# hot_er_lutownica.net
KiCad netlist of a schematic drawn in EAGLE
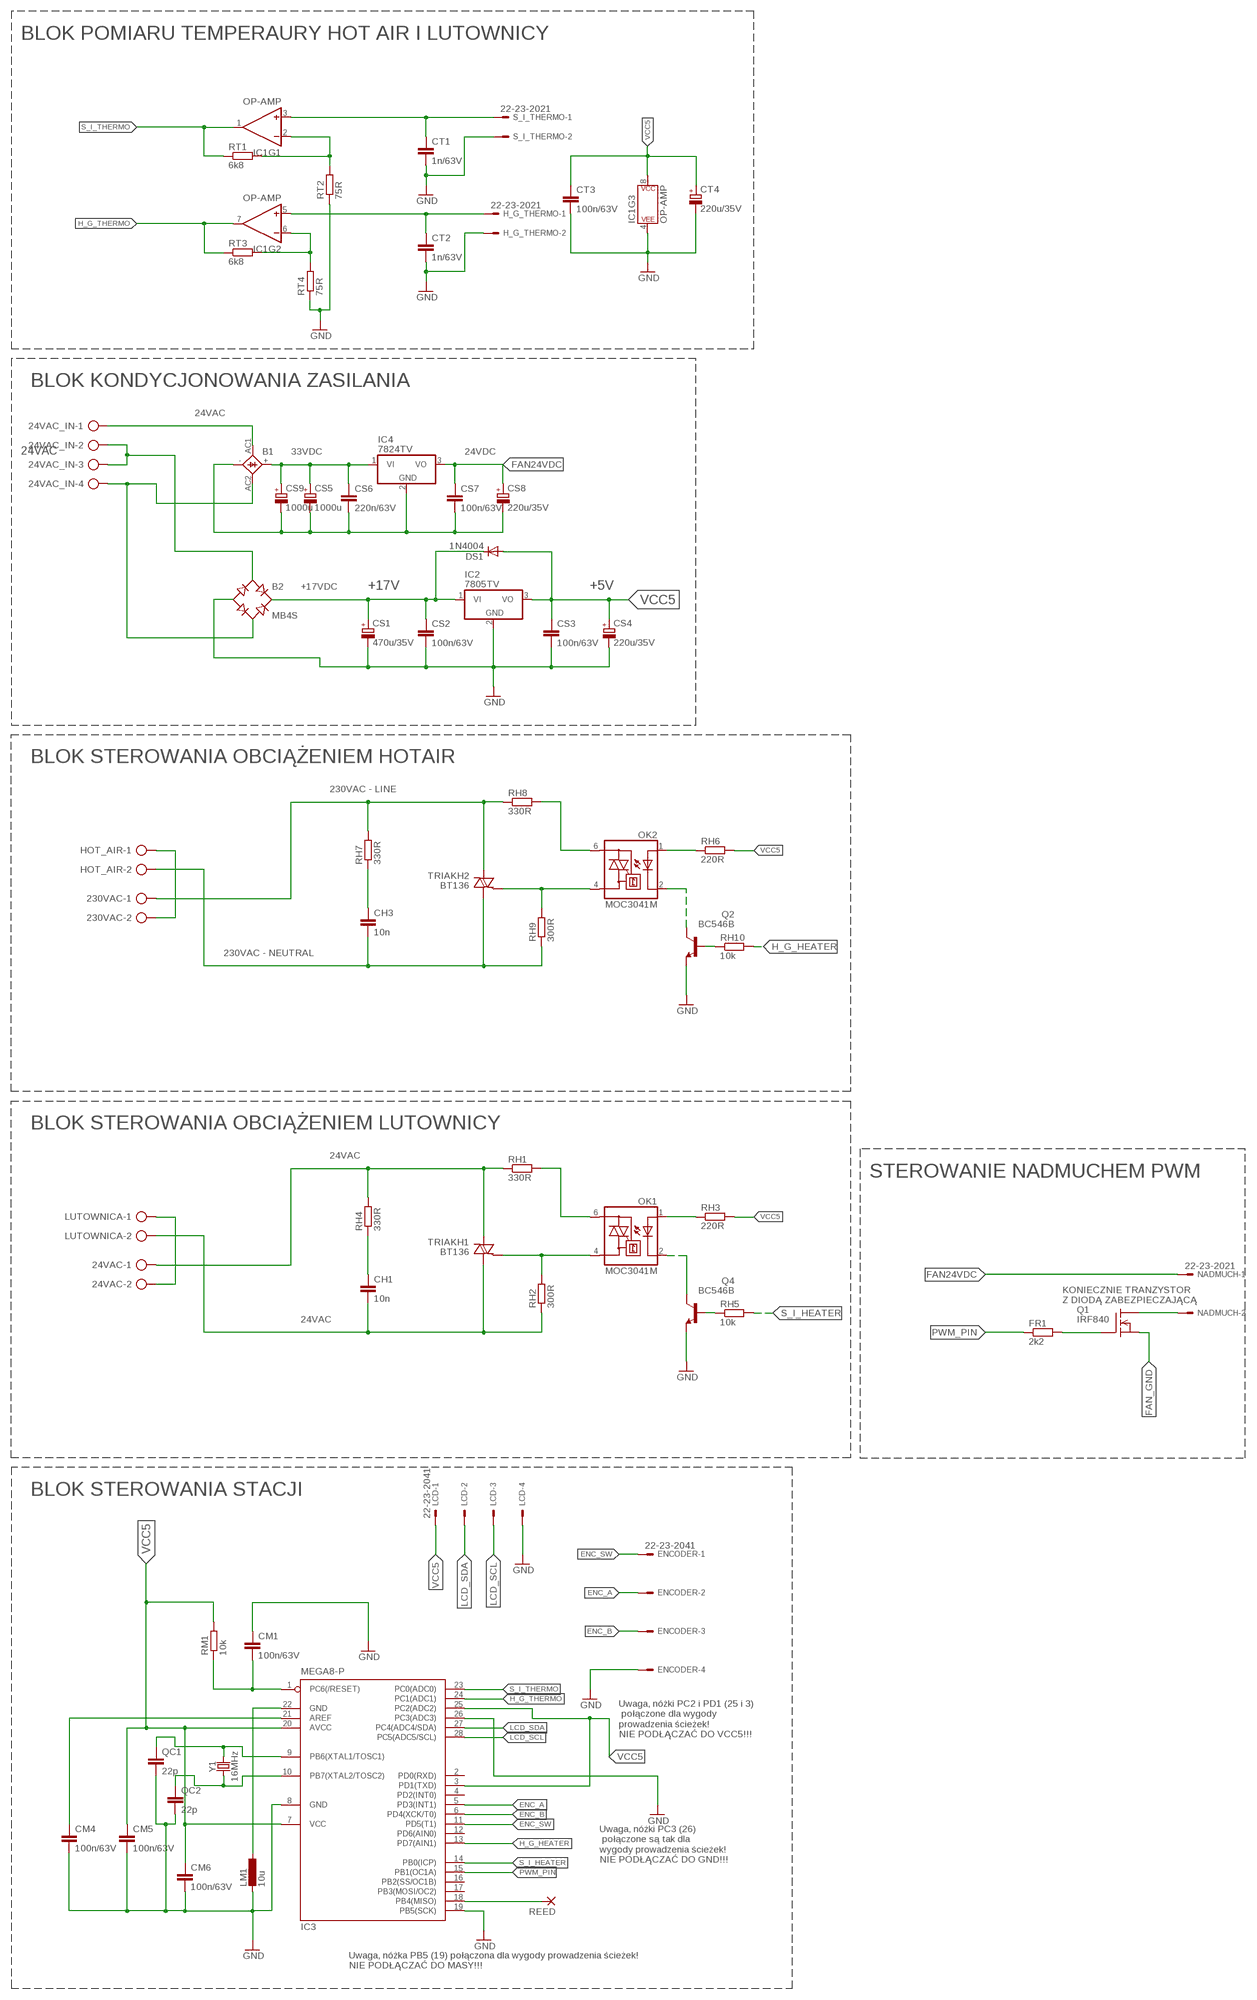
[diagram p0: schematic, sheet 1]

(export (version "E")
  (design (tool "Eeschema 10.0.6"))
  (components
    (comp (ref "24VAC")
      (value "AK500/2")
      (footprint "eagle-import:AK500_2")
      (libsource (lib "eagle-import") (part "AK500/2"))
    )
    (comp (ref "24VAC_IN")
      (value "AK500/4")
      (footprint "eagle-import:AK500_4")
      (libsource (lib "eagle-import") (part "AK500/4"))
    )
    (comp (ref "230VAC")
      (value "AK500/2")
      (footprint "eagle-import:AK500_2")
      (libsource (lib "eagle-import") (part "AK500/2"))
    )
    (comp (ref "B1")
      (value "2KBB-R")
      (footprint "eagle-import:2KBB-R")
      (libsource (lib "eagle-import") (part "2KBB-R"))
    )
    (comp (ref "B2")
      (value "MB4S")
      (footprint "eagle-import:SOIC-4")
      (libsource (lib "eagle-import") (part "MBS4"))
    )
    (comp (ref "CH1")
      (value "10n")
      (footprint "eagle-import:C102-043X133")
      (libsource (lib "eagle-import") (part "C-EU102-043X133"))
    )
    (comp (ref "CH3")
      (value "10n")
      (footprint "eagle-import:C102-043X133")
      (libsource (lib "eagle-import") (part "C-EU102-043X133"))
    )
    (comp (ref "CM1")
      (value "100n/63V")
      (footprint "eagle-import:C050-024X044")
      (libsource (lib "eagle-import") (part "C-EU050-024X044"))
    )
    (comp (ref "CM4")
      (value "100n/63V")
      (footprint "eagle-import:C050-024X044")
      (libsource (lib "eagle-import") (part "C-EU050-024X044"))
    )
    (comp (ref "CM5")
      (value "100n/63V")
      (footprint "eagle-import:C050-024X044")
      (libsource (lib "eagle-import") (part "C-EU050-024X044"))
    )
    (comp (ref "CM6")
      (value "100n/63V")
      (footprint "eagle-import:C050-024X044")
      (libsource (lib "eagle-import") (part "C-EU050-024X044"))
    )
    (comp (ref "CS1")
      (value "470u/35V")
      (footprint "eagle-import:B45181A")
      (libsource (lib "eagle-import") (part "CPOL-EUB45181A"))
    )
    (comp (ref "CS2")
      (value "100n/63V")
      (footprint "eagle-import:C050-024X044")
      (libsource (lib "eagle-import") (part "C-EU050-024X044"))
    )
    (comp (ref "CS3")
      (value "100n/63V")
      (footprint "eagle-import:C050-024X044")
      (libsource (lib "eagle-import") (part "C-EU050-024X044"))
    )
    (comp (ref "CS4")
      (value "220u/35V")
      (footprint "eagle-import:B45181A")
      (libsource (lib "eagle-import") (part "CPOL-EUB45181A"))
    )
    (comp (ref "CS5")
      (value "1000u")
      (footprint "eagle-import:E3,5-8")
      (libsource (lib "eagle-import") (part "CPOL-EUE3.5-8"))
    )
    (comp (ref "CS6")
      (value "220n/63V")
      (footprint "eagle-import:C050-024X044")
      (libsource (lib "eagle-import") (part "C-EU050-024X044"))
    )
    (comp (ref "CS7")
      (value "100n/63V")
      (footprint "eagle-import:C050-024X044")
      (libsource (lib "eagle-import") (part "C-EU050-024X044"))
    )
    (comp (ref "CS8")
      (value "220u/35V")
      (footprint "eagle-import:B45181A")
      (libsource (lib "eagle-import") (part "CPOL-EUB45181A"))
    )
    (comp (ref "CS9")
      (value "1000u")
      (footprint "eagle-import:E3,5-8")
      (libsource (lib "eagle-import") (part "CPOL-EUE3.5-8"))
    )
    (comp (ref "CT1")
      (value "1n/63V")
      (footprint "eagle-import:C050-024X044")
      (libsource (lib "eagle-import") (part "C-EU050-024X044"))
    )
    (comp (ref "CT2")
      (value "1n/63V")
      (footprint "eagle-import:C050-024X044")
      (libsource (lib "eagle-import") (part "C-EU050-024X044"))
    )
    (comp (ref "CT3")
      (value "100n/63V")
      (footprint "eagle-import:C050-024X044")
      (libsource (lib "eagle-import") (part "C-EU050-024X044"))
    )
    (comp (ref "CT4")
      (value "220u/35V")
      (footprint "eagle-import:B45181B")
      (libsource (lib "eagle-import") (part "CPOL-EUB45181B"))
    )
    (comp (ref "DS1")
      (value "1N4004")
      (footprint "eagle-import:DO41-10")
      (libsource (lib "eagle-import") (part "1N4004"))
    )
    (comp (ref "ENCODER")
      (value "22-23-2041")
      (footprint "eagle-import:22-23-2041")
      (fields (field (name "MF") "MOLEX"))
      (libsource (lib "eagle-import") (part "22-23-2041"))
    )
    (comp (ref "FR1")
      (value "2k2")
      (footprint "eagle-import:R0805")
      (libsource (lib "eagle-import") (part "R-EU_R0805"))
    )
    (comp (ref "HOT_AIR")
      (value "AK500/2")
      (footprint "eagle-import:AK500_2")
      (libsource (lib "eagle-import") (part "AK500/2"))
    )
    (comp (ref "H_G_THERMO")
      (value "22-23-2021")
      (footprint "eagle-import:22-23-2021")
      (fields (field (name "MF") "MOLEX"))
      (libsource (lib "eagle-import") (part "22-23-2021"))
    )
    (comp (ref "IC1")
      (value "OP-AMP")
      (footprint "eagle-import:DIP08")
      (libsource (lib "eagle-import") (part "OPAMP-DUALDIP"))
    )
    (comp (ref "IC2")
      (value "7805TV")
      (footprint "eagle-import:TO220V")
      (libsource (lib "eagle-import") (part "78TV05"))
    )
    (comp (ref "IC3")
      (value "MEGA8-P")
      (footprint "eagle-import:DIL28-3")
      (libsource (lib "eagle-import") (part "MEGA8-P"))
    )
    (comp (ref "IC4")
      (value "7824TV")
      (footprint "eagle-import:TO220V")
      (libsource (lib "eagle-import") (part "78TV24"))
    )
    (comp (ref "LCD")
      (value "22-23-2041")
      (footprint "eagle-import:22-23-2041")
      (fields (field (name "MF") "MOLEX"))
      (libsource (lib "eagle-import") (part "22-23-2041"))
    )
    (comp (ref "LM1")
      (value "10u")
      (footprint "eagle-import:0207_10")
      (libsource (lib "eagle-import") (part "L-EU0207/10"))
    )
    (comp (ref "LUTOWNICA")
      (value "AK500/2")
      (footprint "eagle-import:AK500_2")
      (libsource (lib "eagle-import") (part "AK500/2"))
    )
    (comp (ref "NADMUCH")
      (value "22-23-2021")
      (footprint "eagle-import:22-23-2021")
      (fields (field (name "MF") "MOLEX"))
      (libsource (lib "eagle-import") (part "22-23-2021"))
    )
    (comp (ref "OK1")
      (value "MOC3041M")
      (footprint "eagle-import:DIL06")
      (fields (field (name "MF") "FAIRCHILD SEMICONDUCTOR"))
      (libsource (lib "eagle-import") (part "MOC3041M"))
    )
    (comp (ref "OK2")
      (value "MOC3041M")
      (footprint "eagle-import:DIL06")
      (fields (field (name "MF") "FAIRCHILD SEMICONDUCTOR"))
      (libsource (lib "eagle-import") (part "MOC3041M"))
    )
    (comp (ref "Q1")
      (value "IRF840")
      (footprint "eagle-import:TO220")
      (libsource (lib "eagle-import") (part "IRF840"))
    )
    (comp (ref "Q2")
      (value "BC546B")
      (footprint "eagle-import:TO92-EBC")
      (libsource (lib "eagle-import") (part "BC546B"))
    )
    (comp (ref "Q4")
      (value "BC546B")
      (footprint "eagle-import:TO92-EBC")
      (libsource (lib "eagle-import") (part "BC546B"))
    )
    (comp (ref "QC1")
      (value "22p")
      (footprint "eagle-import:C0805K")
      (libsource (lib "eagle-import") (part "C-EUC0805K"))
    )
    (comp (ref "QC2")
      (value "22p")
      (footprint "eagle-import:C0805K")
      (libsource (lib "eagle-import") (part "C-EUC0805K"))
    )
    (comp (ref "REED")
      (value "2,54/0,9")
      (footprint "eagle-import:2,54_0,9")
      (libsource (lib "eagle-import") (part "2,54/0,9"))
    )
    (comp (ref "RH1")
      (value "330R")
      (footprint "eagle-import:0204_7")
      (libsource (lib "eagle-import") (part "R-EU_0204/7"))
    )
    (comp (ref "RH2")
      (value "300R")
      (footprint "eagle-import:0204_5")
      (libsource (lib "eagle-import") (part "R-EU_0204/5"))
    )
    (comp (ref "RH3")
      (value "220R")
      (footprint "eagle-import:0204_5")
      (libsource (lib "eagle-import") (part "R-EU_0204/5"))
    )
    (comp (ref "RH4")
      (value "330R")
      (footprint "eagle-import:0204_5")
      (libsource (lib "eagle-import") (part "R-EU_0204/5"))
    )
    (comp (ref "RH5")
      (value "10k")
      (footprint "eagle-import:0204_7")
      (libsource (lib "eagle-import") (part "R-EU_0204/7"))
    )
    (comp (ref "RH6")
      (value "220R")
      (footprint "eagle-import:0204_7")
      (libsource (lib "eagle-import") (part "R-EU_0204/7"))
    )
    (comp (ref "RH7")
      (value "330R")
      (footprint "eagle-import:0204_7")
      (libsource (lib "eagle-import") (part "R-EU_0204/7"))
    )
    (comp (ref "RH8")
      (value "330R")
      (footprint "eagle-import:0207_10")
      (libsource (lib "eagle-import") (part "R-EU_0207/10"))
    )
    (comp (ref "RH9")
      (value "300R")
      (footprint "eagle-import:0204_5")
      (libsource (lib "eagle-import") (part "R-EU_0204/5"))
    )
    (comp (ref "RH10")
      (value "10k")
      (footprint "eagle-import:0207_12")
      (libsource (lib "eagle-import") (part "R-EU_0207/12"))
    )
    (comp (ref "RM1")
      (value "10k")
      (footprint "eagle-import:R0805")
      (libsource (lib "eagle-import") (part "R-EU_R0805"))
    )
    (comp (ref "RT1")
      (value "6k8")
      (footprint "eagle-import:0207_2V")
      (libsource (lib "eagle-import") (part "R-EU_0207/2V"))
    )
    (comp (ref "RT2")
      (value "75R")
      (footprint "eagle-import:0207_2V")
      (libsource (lib "eagle-import") (part "R-EU_0207/2V"))
    )
    (comp (ref "RT3")
      (value "6k8")
      (footprint "eagle-import:0207_2V")
      (libsource (lib "eagle-import") (part "R-EU_0207/2V"))
    )
    (comp (ref "RT4")
      (value "75R")
      (footprint "eagle-import:0207_2V")
      (libsource (lib "eagle-import") (part "R-EU_0207/2V"))
    )
    (comp (ref "S_I_THERMO")
      (value "22-23-2021")
      (footprint "eagle-import:22-23-2021")
      (fields (field (name "MF") "MOLEX"))
      (libsource (lib "eagle-import") (part "22-23-2021"))
    )
    (comp (ref "TRIAKH1")
      (value "BT136")
      (footprint "eagle-import:TO220AB")
      (libsource (lib "eagle-import") (part "BT136"))
    )
    (comp (ref "TRIAKH2")
      (value "BT136")
      (footprint "eagle-import:TO220AB")
      (libsource (lib "eagle-import") (part "BT136"))
    )
    (comp (ref "Y1")
      (value "16MHz")
      (footprint "eagle-import:HC49U")
      (libsource (lib "eagle-import") (part "CRYSTALPTH-HC49UV"))
    )
  )
  (nets
    (net (code "1") (name "ENC_A") (class "Default")
      (node (ref "ENCODER") (pin "2") (pinfunction "S_2") (pintype "passive"))
      (node (ref "IC3") (pin "5") (pinfunction "PD3(INT1)_5") (pintype "bidirectional"))
    )
    (net (code "2") (name "ENC_B") (class "Default")
      (node (ref "ENCODER") (pin "3") (pinfunction "S_3") (pintype "passive"))
      (node (ref "IC3") (pin "6") (pinfunction "PD4(XCK/T0)_6") (pintype "bidirectional"))
    )
    (net (code "3") (name "ENC_SW") (class "Default")
      (node (ref "ENCODER") (pin "1") (pinfunction "S_1") (pintype "passive"))
      (node (ref "IC3") (pin "11") (pinfunction "PD5(T1)_11") (pintype "bidirectional"))
    )
    (net (code "4") (name "FAN24VDC") (class "Default")
      (node (ref "CS7") (pin "1") (pinfunction "1_1") (pintype "passive"))
      (node (ref "CS8") (pin "+") (pinfunction "+_+") (pintype "passive"))
      (node (ref "IC4") (pin "3") (pinfunction "VO_3") (pintype "passive"))
      (node (ref "NADMUCH") (pin "1") (pinfunction "S_1") (pintype "passive"))
    )
    (net (code "5") (name "FAN_GND") (class "Default")
      (node (ref "B1") (pin "-") (pinfunction "-_-") (pintype "passive"))
      (node (ref "CS5") (pin "-") (pinfunction "-_-") (pintype "passive"))
      (node (ref "CS6") (pin "2") (pinfunction "2_2") (pintype "passive"))
      (node (ref "CS7") (pin "2") (pinfunction "2_2") (pintype "passive"))
      (node (ref "CS8") (pin "-") (pinfunction "-_-") (pintype "passive"))
      (node (ref "CS9") (pin "-") (pinfunction "-_-") (pintype "passive"))
      (node (ref "IC4") (pin "2") (pinfunction "GND_2") (pintype "passive"))
      (node (ref "Q1") (pin "3") (pinfunction "S_3") (pintype "passive"))
    )
    (net (code "6") (name "GND") (class "Default")
      (node (ref "B2") (pin "-") (pinfunction "-_-") (pintype "passive"))
      (node (ref "CM1") (pin "1") (pinfunction "1_1") (pintype "passive"))
      (node (ref "CM4") (pin "2") (pinfunction "2_2") (pintype "passive"))
      (node (ref "CM5") (pin "2") (pinfunction "2_2") (pintype "passive"))
      (node (ref "CM6") (pin "2") (pinfunction "2_2") (pintype "passive"))
      (node (ref "CS1") (pin "-") (pinfunction "-_-") (pintype "passive"))
      (node (ref "CS2") (pin "2") (pinfunction "2_2") (pintype "passive"))
      (node (ref "CS3") (pin "2") (pinfunction "2_2") (pintype "passive"))
      (node (ref "CS4") (pin "-") (pinfunction "-_-") (pintype "passive"))
      (node (ref "CT1") (pin "2") (pinfunction "2_2") (pintype "passive"))
      (node (ref "CT2") (pin "2") (pinfunction "2_2") (pintype "passive"))
      (node (ref "CT3") (pin "2") (pinfunction "2_2") (pintype "passive"))
      (node (ref "CT4") (pin "-") (pinfunction "-_-") (pintype "passive"))
      (node (ref "ENCODER") (pin "4") (pinfunction "S_4") (pintype "passive"))
      (node (ref "H_G_THERMO") (pin "2") (pinfunction "S_2") (pintype "passive"))
      (node (ref "IC1") (pin "4") (pinfunction "P$V-_4") (pintype "bidirectional"))
      (node (ref "IC2") (pin "2") (pinfunction "GND_2") (pintype "passive"))
      (node (ref "IC3") (pin "19") (pinfunction "PB5(SCK)_19") (pintype "bidirectional"))
      (node (ref "IC3") (pin "26") (pinfunction "PC3(ADC3)_26") (pintype "bidirectional"))
      (node (ref "IC3") (pin "8") (pinfunction "GND_8") (pintype "power_in"))
      (node (ref "LCD") (pin "4") (pinfunction "S_4") (pintype "passive"))
      (node (ref "LM1") (pin "2") (pinfunction "2_2") (pintype "passive"))
      (node (ref "Q2") (pin "E") (pinfunction "E_E") (pintype "passive"))
      (node (ref "Q4") (pin "E") (pinfunction "E_E") (pintype "passive"))
      (node (ref "QC1") (pin "2") (pinfunction "2_2") (pintype "passive"))
      (node (ref "QC2") (pin "2") (pinfunction "2_2") (pintype "passive"))
      (node (ref "RT2") (pin "1") (pinfunction "1_1") (pintype "passive"))
      (node (ref "RT4") (pin "1") (pinfunction "1_1") (pintype "passive"))
      (node (ref "S_I_THERMO") (pin "2") (pinfunction "S_2") (pintype "passive"))
    )
    (net (code "7") (name "H_G_HEATER") (class "Default")
      (node (ref "IC3") (pin "13") (pinfunction "PD7(AIN1)_13") (pintype "bidirectional"))
      (node (ref "RH10") (pin "2") (pinfunction "2_2") (pintype "passive"))
    )
    (net (code "8") (name "H_G_THERMO") (class "Default")
      (node (ref "IC1") (pin "7") (pinfunction "OUT_7") (pintype "output"))
      (node (ref "IC3") (pin "24") (pinfunction "PC1(ADC1)_24") (pintype "bidirectional"))
      (node (ref "RT3") (pin "1") (pinfunction "1_1") (pintype "passive"))
    )
    (net (code "9") (name "LCD_SCL") (class "Default")
      (node (ref "IC3") (pin "28") (pinfunction "PC5(ADC5/SCL)_28") (pintype "bidirectional"))
      (node (ref "LCD") (pin "3") (pinfunction "S_3") (pintype "passive"))
    )
    (net (code "10") (name "LCD_SDA") (class "Default")
      (node (ref "IC3") (pin "27") (pinfunction "PC4(ADC4/SDA)_27") (pintype "bidirectional"))
      (node (ref "LCD") (pin "2") (pinfunction "S_2") (pintype "passive"))
    )
    (net (code "11") (name "Net-(24VACA-KL)") (class "Default")
      (node (ref "24VAC") (pin "1") (pinfunction "KL_1") (pintype "passive"))
      (node (ref "RH1") (pin "1") (pinfunction "1_1") (pintype "passive"))
      (node (ref "RH4") (pin "2") (pinfunction "2_2") (pintype "passive"))
      (node (ref "TRIAKH1") (pin "2") (pinfunction "A2_2") (pintype "passive"))
    )
    (net (code "12") (name "Net-(24VACB-KL)") (class "Default")
      (node (ref "24VAC") (pin "2") (pinfunction "KL_2") (pintype "passive"))
      (node (ref "LUTOWNICA") (pin "1") (pinfunction "KL_1") (pintype "passive"))
    )
    (net (code "13") (name "Net-(24VAC_INA-KL)") (class "Default")
      (node (ref "24VAC_IN") (pin "1") (pinfunction "KL_1") (pintype "passive"))
      (node (ref "B1") (pin "AC1") (pinfunction "AC1_AC1") (pintype "passive"))
    )
    (net (code "14") (name "Net-(24VAC_INB-KL)") (class "Default")
      (node (ref "24VAC_IN") (pin "2") (pinfunction "KL_2") (pintype "passive"))
      (node (ref "24VAC_IN") (pin "3") (pinfunction "KL_3") (pintype "passive"))
      (node (ref "B2") (pin "~1") (pinfunction "AC1_~1") (pintype "passive"))
    )
    (net (code "15") (name "Net-(24VAC_IND-KL)") (class "Default")
      (node (ref "24VAC_IN") (pin "4") (pinfunction "KL_4") (pintype "passive"))
      (node (ref "B1") (pin "AC2") (pinfunction "AC2_AC2") (pintype "passive"))
      (node (ref "B2") (pin "~2") (pinfunction "AC2_~2") (pintype "passive"))
    )
    (net (code "16") (name "Net-(230VACA-KL)") (class "Default")
      (node (ref "230VAC") (pin "1") (pinfunction "KL_1") (pintype "passive"))
      (node (ref "RH7") (pin "2") (pinfunction "2_2") (pintype "passive"))
      (node (ref "RH8") (pin "1") (pinfunction "1_1") (pintype "passive"))
      (node (ref "TRIAKH2") (pin "2") (pinfunction "A2_2") (pintype "passive"))
    )
    (net (code "17") (name "Net-(230VACB-KL)") (class "Default")
      (node (ref "230VAC") (pin "2") (pinfunction "KL_2") (pintype "passive"))
      (node (ref "HOT_AIR") (pin "1") (pinfunction "KL_1") (pintype "passive"))
    )
    (net (code "18") (name "Net-(CH1-Pad1)") (class "Default")
      (node (ref "CH1") (pin "1") (pinfunction "1_1") (pintype "passive"))
      (node (ref "RH4") (pin "1") (pinfunction "1_1") (pintype "passive"))
    )
    (net (code "19") (name "Net-(CH3-Pad1)") (class "Default")
      (node (ref "CH3") (pin "1") (pinfunction "1_1") (pintype "passive"))
      (node (ref "RH7") (pin "1") (pinfunction "1_1") (pintype "passive"))
    )
    (net (code "20") (name "Net-(HOT_AIRB-KL)") (class "Default")
      (node (ref "CH3") (pin "2") (pinfunction "2_2") (pintype "passive"))
      (node (ref "HOT_AIR") (pin "2") (pinfunction "KL_2") (pintype "passive"))
      (node (ref "RH9") (pin "1") (pinfunction "1_1") (pintype "passive"))
      (node (ref "TRIAKH2") (pin "1") (pinfunction "A1_1") (pintype "passive"))
    )
    (net (code "21") (name "Net-(H_G_THERMOA-S)") (class "Default")
      (node (ref "CT2") (pin "1") (pinfunction "1_1") (pintype "passive"))
      (node (ref "H_G_THERMO") (pin "1") (pinfunction "S_1") (pintype "passive"))
      (node (ref "IC1") (pin "5") (pinfunction "+IN_5") (pintype "input"))
    )
    (net (code "22") (name "Net-(IC1A-+IN)") (class "Default")
      (node (ref "CT1") (pin "1") (pinfunction "1_1") (pintype "passive"))
      (node (ref "IC1") (pin "3") (pinfunction "+IN_3") (pintype "input"))
      (node (ref "S_I_THERMO") (pin "1") (pinfunction "S_1") (pintype "passive"))
    )
    (net (code "23") (name "Net-(IC1A--IN)") (class "Default")
      (node (ref "IC1") (pin "2") (pinfunction "-IN_2") (pintype "input"))
      (node (ref "RT1") (pin "2") (pinfunction "2_2") (pintype "passive"))
      (node (ref "RT2") (pin "2") (pinfunction "2_2") (pintype "passive"))
    )
    (net (code "24") (name "Net-(IC1B--IN)") (class "Default")
      (node (ref "IC1") (pin "6") (pinfunction "-IN_6") (pintype "input"))
      (node (ref "RT3") (pin "2") (pinfunction "2_2") (pintype "passive"))
      (node (ref "RT4") (pin "2") (pinfunction "2_2") (pintype "passive"))
    )
    (net (code "25") (name "Net-(IC2-VI)") (class "Default")
      (node (ref "B2") (pin "+") (pinfunction "+_+") (pintype "passive"))
      (node (ref "CS1") (pin "+") (pinfunction "+_+") (pintype "passive"))
      (node (ref "CS2") (pin "1") (pinfunction "1_1") (pintype "passive"))
      (node (ref "DS1") (pin "C") (pinfunction "C_C") (pintype "passive"))
      (node (ref "IC2") (pin "1") (pinfunction "VI_1") (pintype "input"))
    )
    (net (code "26") (name "Net-(IC3-AREF)") (class "Default")
      (node (ref "CM4") (pin "1") (pinfunction "1_1") (pintype "passive"))
      (node (ref "IC3") (pin "21") (pinfunction "AREF_21") (pintype "passive"))
    )
    (net (code "27") (name "Net-(IC3-GND-Pad22)") (class "Default")
      (node (ref "IC3") (pin "22") (pinfunction "GND_22") (pintype "power_in"))
      (node (ref "LM1") (pin "1") (pinfunction "1_1") (pintype "passive"))
    )
    (net (code "28") (name "Net-(IC3-PB4(MISO))") (class "Default")
      (node (ref "IC3") (pin "18") (pinfunction "PB4(MISO)_18") (pintype "bidirectional"))
      (node (ref "REED") (pin "1") (pinfunction "P_1") (pintype "passive"))
    )
    (net (code "29") (name "Net-(IC3-PB6(XTAL1{slash}TOSC1))") (class "Default")
      (node (ref "IC3") (pin "9") (pinfunction "PB6(XTAL1/TOSC1)_9") (pintype "bidirectional"))
      (node (ref "QC1") (pin "1") (pinfunction "1_1") (pintype "passive"))
      (node (ref "Y1") (pin "2") (pinfunction "2_2") (pintype "passive"))
    )
    (net (code "30") (name "Net-(IC3-PB7(XTAL2{slash}TOSC2))") (class "Default")
      (node (ref "IC3") (pin "10") (pinfunction "PB7(XTAL2/TOSC2)_10") (pintype "bidirectional"))
      (node (ref "QC2") (pin "1") (pinfunction "1_1") (pintype "passive"))
      (node (ref "Y1") (pin "1") (pinfunction "1_1") (pintype "passive"))
    )
    (net (code "31") (name "Net-(IC3-PC6({slash}RESET))") (class "Default")
      (node (ref "CM1") (pin "2") (pinfunction "2_2") (pintype "passive"))
      (node (ref "IC3") (pin "1") (pinfunction "PC6(/RESET)_1") (pintype "bidirectional"))
      (node (ref "RM1") (pin "1") (pinfunction "1_1") (pintype "passive"))
    )
    (net (code "32") (name "Net-(IC4-VI)") (class "Default")
      (node (ref "B1") (pin "+") (pinfunction "+_+") (pintype "passive"))
      (node (ref "CS5") (pin "+") (pinfunction "+_+") (pintype "passive"))
      (node (ref "CS6") (pin "1") (pinfunction "1_1") (pintype "passive"))
      (node (ref "CS9") (pin "+") (pinfunction "+_+") (pintype "passive"))
      (node (ref "IC4") (pin "1") (pinfunction "VI_1") (pintype "input"))
    )
    (net (code "33") (name "Net-(LUTOWNICAB-KL)") (class "Default")
      (node (ref "CH1") (pin "2") (pinfunction "2_2") (pintype "passive"))
      (node (ref "LUTOWNICA") (pin "2") (pinfunction "KL_2") (pintype "passive"))
      (node (ref "RH2") (pin "1") (pinfunction "1_1") (pintype "passive"))
      (node (ref "TRIAKH1") (pin "1") (pinfunction "A1_1") (pintype "passive"))
    )
    (net (code "34") (name "Net-(NADMUCHB-S)") (class "Default")
      (node (ref "NADMUCH") (pin "2") (pinfunction "S_2") (pintype "passive"))
      (node (ref "Q1") (pin "2") (pinfunction "D_2") (pintype "passive"))
    )
    (net (code "35") (name "Net-(OK1-A)") (class "Default")
      (node (ref "OK1") (pin "1") (pinfunction "A_1") (pintype "passive"))
      (node (ref "RH3") (pin "1") (pinfunction "1_1") (pintype "passive"))
    )
    (net (code "36") (name "Net-(OK1-A1)") (class "Default")
      (node (ref "OK1") (pin "4") (pinfunction "A1_4") (pintype "passive"))
      (node (ref "RH2") (pin "2") (pinfunction "2_2") (pintype "passive"))
      (node (ref "TRIAKH1") (pin "3") (pinfunction "G_3") (pintype "passive"))
    )
    (net (code "37") (name "Net-(OK1-A2)") (class "Default")
      (node (ref "OK1") (pin "6") (pinfunction "A2_6") (pintype "passive"))
      (node (ref "RH1") (pin "2") (pinfunction "2_2") (pintype "passive"))
    )
    (net (code "38") (name "Net-(OK1-C)") (class "Default")
      (node (ref "OK1") (pin "2") (pinfunction "C_2") (pintype "passive"))
      (node (ref "Q4") (pin "C") (pinfunction "C_C") (pintype "passive"))
    )
    (net (code "39") (name "Net-(OK2-A)") (class "Default")
      (node (ref "OK2") (pin "1") (pinfunction "A_1") (pintype "passive"))
      (node (ref "RH6") (pin "1") (pinfunction "1_1") (pintype "passive"))
    )
    (net (code "40") (name "Net-(OK2-A1)") (class "Default")
      (node (ref "OK2") (pin "4") (pinfunction "A1_4") (pintype "passive"))
      (node (ref "RH9") (pin "2") (pinfunction "2_2") (pintype "passive"))
      (node (ref "TRIAKH2") (pin "3") (pinfunction "G_3") (pintype "passive"))
    )
    (net (code "41") (name "Net-(OK2-A2)") (class "Default")
      (node (ref "OK2") (pin "6") (pinfunction "A2_6") (pintype "passive"))
      (node (ref "RH8") (pin "2") (pinfunction "2_2") (pintype "passive"))
    )
    (net (code "42") (name "Net-(OK2-C)") (class "Default")
      (node (ref "OK2") (pin "2") (pinfunction "C_2") (pintype "passive"))
      (node (ref "Q2") (pin "C") (pinfunction "C_C") (pintype "passive"))
    )
    (net (code "43") (name "Net-(Q1-G)") (class "Default")
      (node (ref "FR1") (pin "2") (pinfunction "2_2") (pintype "passive"))
      (node (ref "Q1") (pin "1") (pinfunction "G_1") (pintype "passive"))
    )
    (net (code "44") (name "Net-(Q2-PadB)") (class "Default")
      (node (ref "Q2") (pin "B") (pinfunction "B_B") (pintype "passive"))
      (node (ref "RH10") (pin "1") (pinfunction "1_1") (pintype "passive"))
    )
    (net (code "45") (name "Net-(Q4-PadB)") (class "Default")
      (node (ref "Q4") (pin "B") (pinfunction "B_B") (pintype "passive"))
      (node (ref "RH5") (pin "1") (pinfunction "1_1") (pintype "passive"))
    )
    (net (code "46") (name "PWM_PIN") (class "Default")
      (node (ref "FR1") (pin "1") (pinfunction "1_1") (pintype "passive"))
      (node (ref "IC3") (pin "15") (pinfunction "PB1(OC1A)_15") (pintype "bidirectional"))
    )
    (net (code "47") (name "S_I_HEATER") (class "Default")
      (node (ref "IC3") (pin "14") (pinfunction "PB0(ICP)_14") (pintype "bidirectional"))
      (node (ref "RH5") (pin "2") (pinfunction "2_2") (pintype "passive"))
    )
    (net (code "48") (name "S_I_THERMO") (class "Default")
      (node (ref "IC1") (pin "1") (pinfunction "OUT_1") (pintype "output"))
      (node (ref "IC3") (pin "23") (pinfunction "PC0(ADC0)_23") (pintype "bidirectional"))
      (node (ref "RT1") (pin "1") (pinfunction "1_1") (pintype "passive"))
    )
    (net (code "49") (name "VCC5") (class "Default")
      (node (ref "CM5") (pin "1") (pinfunction "1_1") (pintype "passive"))
      (node (ref "CM6") (pin "1") (pinfunction "1_1") (pintype "passive"))
      (node (ref "CS3") (pin "1") (pinfunction "1_1") (pintype "passive"))
      (node (ref "CS4") (pin "+") (pinfunction "+_+") (pintype "passive"))
      (node (ref "CT3") (pin "1") (pinfunction "1_1") (pintype "passive"))
      (node (ref "CT4") (pin "+") (pinfunction "+_+") (pintype "passive"))
      (node (ref "DS1") (pin "A") (pinfunction "A_A") (pintype "passive"))
      (node (ref "IC1") (pin "8") (pinfunction "P$V+_8") (pintype "bidirectional"))
      (node (ref "IC2") (pin "3") (pinfunction "VO_3") (pintype "passive"))
      (node (ref "IC3") (pin "20") (pinfunction "AVCC_20") (pintype "power_in"))
      (node (ref "IC3") (pin "25") (pinfunction "PC2(ADC2)_25") (pintype "bidirectional"))
      (node (ref "IC3") (pin "3") (pinfunction "PD1(TXD)_3") (pintype "bidirectional"))
      (node (ref "IC3") (pin "7") (pinfunction "VCC_7") (pintype "power_in"))
      (node (ref "LCD") (pin "1") (pinfunction "S_1") (pintype "passive"))
      (node (ref "RH3") (pin "2") (pinfunction "2_2") (pintype "passive"))
      (node (ref "RH6") (pin "2") (pinfunction "2_2") (pintype "passive"))
      (node (ref "RM1") (pin "2") (pinfunction "2_2") (pintype "passive"))
    )
    (net (code "50") (name "unconnected-(IC3-PB2(SS{slash}OC1B)-Pad16)") (class "Default")
      (node (ref "IC3") (pin "16") (pinfunction "PB2(SS/OC1B)_16") (pintype "bidirectional"))
    )
    (net (code "51") (name "unconnected-(IC3-PB3(MOSI{slash}OC2)-Pad17)") (class "Default")
      (node (ref "IC3") (pin "17") (pinfunction "PB3(MOSI/OC2)_17") (pintype "bidirectional"))
    )
    (net (code "52") (name "unconnected-(IC3-PD0(RXD)-Pad2)") (class "Default")
      (node (ref "IC3") (pin "2") (pinfunction "PD0(RXD)_2") (pintype "bidirectional"))
    )
    (net (code "53") (name "unconnected-(IC3-PD2(INT0)-Pad4)") (class "Default")
      (node (ref "IC3") (pin "4") (pinfunction "PD2(INT0)_4") (pintype "bidirectional"))
    )
    (net (code "54") (name "unconnected-(IC3-PD6(AIN0)-Pad12)") (class "Default")
      (node (ref "IC3") (pin "12") (pinfunction "PD6(AIN0)_12") (pintype "bidirectional"))
    )
  )
)
